# Thrust-Schematic.net
KiCad netlist of a schematic drawn in Altium Designer
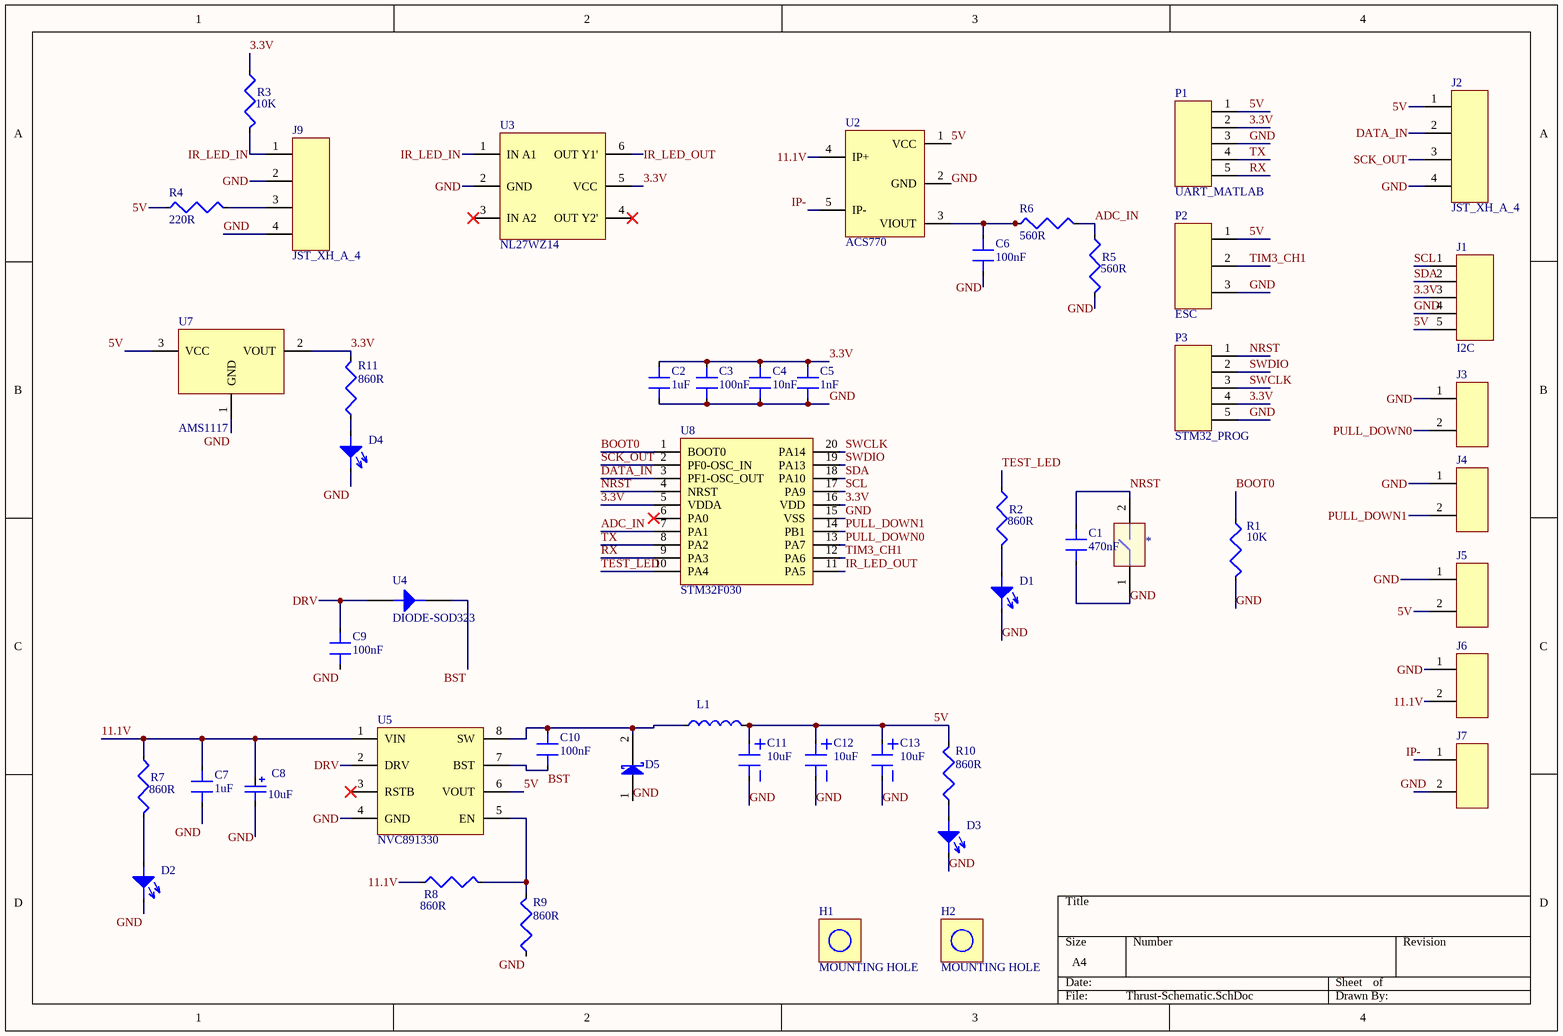
[diagram p0: Thrust-Schematic.SchDoc]

(export (version "E")
  (design (tool "Eeschema 10.0.6"))
  (components
    (comp (ref "*") (value "SWITCH") (footprint "SWITCH") (libsource (lib "Schlib1") (part "SWITCH")))
    (comp (ref "C1") (value "470nF") (footprint "RES0805") (libsource (lib "Schlib1") (part "CAP0805")))
    (comp (ref "C2") (value "1uF") (footprint "RES0805") (libsource (lib "Schlib1") (part "CAP0805")))
    (comp (ref "C3") (value "100nF") (footprint "RES0805") (libsource (lib "Schlib1") (part "CAP0805")))
    (comp (ref "C4") (value "10nF") (footprint "RES0805") (libsource (lib "Schlib1") (part "CAP0805")))
    (comp (ref "C5") (value "1nF") (footprint "RES0805") (libsource (lib "Schlib1") (part "CAP0805")))
    (comp (ref "C6") (value "100nF") (footprint "RES0805") (libsource (lib "Schlib1") (part "CAP0805")))
    (comp (ref "C7") (value "1uF") (footprint "RES0805") (libsource (lib "Schlib1") (part "CAP0805")))
    (comp (ref "C8")
      (value "10uF")
      (footprint "Cap_4x5.4_SMD")
      (libsource (lib "Schlib1") (part "SMD_Cap_4x5.4"))
    )
    (comp (ref "C9") (value "100nF") (footprint "RES0805") (libsource (lib "Schlib1") (part "CAP0805")))
    (comp (ref "C10") (value "100nF") (footprint "RES0805") (libsource (lib "Schlib1") (part "CAP0805")))
    (comp (ref "C11") (value "10uF") (footprint "CAP_THT") (libsource (lib "Schlib1") (part "CAP_THT")))
    (comp (ref "C12") (value "10uF") (footprint "CAP_THT") (libsource (lib "Schlib1") (part "CAP_THT")))
    (comp (ref "C13") (value "10uF") (footprint "CAP_THT") (libsource (lib "Schlib1") (part "CAP_THT")))
    (comp (ref "D1") (value "LED0805") (footprint "RES0805") (libsource (lib "Schlib1") (part "LED0805")))
    (comp (ref "D2") (value "LED0805") (footprint "RES0805") (libsource (lib "Schlib1") (part "LED0805")))
    (comp (ref "D3") (value "LED0805") (footprint "RES0805") (libsource (lib "Schlib1") (part "LED0805")))
    (comp (ref "D4") (value "LED0805") (footprint "RES0805") (libsource (lib "Schlib1") (part "LED0805")))
    (comp (ref "D5")
      (value "Diode")
      (footprint "Schottky")
      (description "Schottky Diode")
      (libsource (lib "Trig_Schlib") (part "Schottyky Diode"))
    )
    (comp (ref "H1")
      (value "MOUNTING HOLE")
      (footprint "MOUNTING HOLE")
      (libsource (lib "Trig_Schlib") (part "MOUNTING HOLE"))
    )
    (comp (ref "H2")
      (value "MOUNTING HOLE")
      (footprint "MOUNTING HOLE")
      (libsource (lib "Trig_Schlib") (part "MOUNTING HOLE"))
    )
    (comp (ref "J1") (value "I2C") (footprint "JST_XH_A_5") (libsource (lib "Schlib1") (part "JST_XH_A_5")))
    (comp (ref "J2")
      (value "JST_XH_A_4")
      (footprint "JST_XH_A_4")
      (libsource (lib "Schlib1") (part "JST_XH_A_4"))
    )
    (comp (ref "J3")
      (value "JST_XH_A_2")
      (footprint "JST_XH_A_2")
      (libsource (lib "Schlib1") (part "JST_XH_A_2"))
    )
    (comp (ref "J4")
      (value "JST_XH_A_2")
      (footprint "JST_XH_A_2")
      (libsource (lib "Schlib1") (part "JST_XH_A_2"))
    )
    (comp (ref "J5")
      (value "JST_XH_A_2")
      (footprint "JST_XH_A_2")
      (libsource (lib "Schlib1") (part "JST_XH_A_2"))
    )
    (comp (ref "J6") (value "XT60") (footprint "XT60") (libsource (lib "Schlib1") (part "XT60")))
    (comp (ref "J7") (value "XT60") (footprint "XT60") (libsource (lib "Schlib1") (part "XT60")))
    (comp (ref "J9")
      (value "JST_XH_A_4")
      (footprint "JST_XH_A_4")
      (libsource (lib "Schlib1") (part "JST_XH_A_4"))
    )
    (comp (ref "L1")
      (value "INDUCTOR")
      (footprint "IND-IHLP-1212BZ-11")
      (description "IHLP-1212BZ-11")
      (libsource (lib "Schlib1") (part "INDUCTOR"))
    )
    (comp (ref "P1")
      (value "UART_MATLAB")
      (footprint "Pin_Header_1x5")
      (libsource (lib "Schlib1") (part "Pin_Header_1x5"))
    )
    (comp (ref "P2")
      (value "ESC")
      (footprint "Pin_Header_1x3")
      (libsource (lib "Schlib1") (part "Pin_Header_1x3"))
    )
    (comp (ref "P3")
      (value "STM32_PROG")
      (footprint "Pin_Header_1x5")
      (libsource (lib "Schlib1") (part "Pin_Header_1x5"))
    )
    (comp (ref "R1") (value "10K") (footprint "RES0805") (libsource (lib "Schlib1") (part "RES0805")))
    (comp (ref "R2") (value "860R") (footprint "RES0805") (libsource (lib "Schlib1") (part "RES0805")))
    (comp (ref "R3") (value "10K") (footprint "RES0805") (libsource (lib "Schlib1") (part "RES0805")))
    (comp (ref "R4") (value "220R") (footprint "RES0805") (libsource (lib "Schlib1") (part "RES0805")))
    (comp (ref "R5") (value "560R") (footprint "RES0805") (libsource (lib "Schlib1") (part "RES0805")))
    (comp (ref "R6") (value "560R") (footprint "RES0805") (libsource (lib "Schlib1") (part "RES0805")))
    (comp (ref "R7") (value "860R") (footprint "RES0805") (libsource (lib "Schlib1") (part "RES0805")))
    (comp (ref "R8") (value "860R") (footprint "RES0805") (libsource (lib "Schlib1") (part "RES0805")))
    (comp (ref "R9") (value "860R") (footprint "RES0805") (libsource (lib "Schlib1") (part "RES0805")))
    (comp (ref "R10") (value "860R") (footprint "RES0805") (libsource (lib "Schlib1") (part "RES0805")))
    (comp (ref "R11") (value "860R") (footprint "RES0805") (libsource (lib "Schlib1") (part "RES0805")))
    (comp (ref "U2") (value "ACS770") (footprint "ACS770") (libsource (lib "Schlib1") (part "ACS770")))
    (comp (ref "U3") (value "NL27WZ14") (footprint "TSOP6") (libsource (lib "Schlib1") (part "NL27WZ14")))
    (comp (ref "U4")
      (value "DIODE-SOD323")
      (footprint "SODFL250X100-2N")
      (libsource (lib "Schlib1") (part "DIODE-SOD323"))
    )
    (comp (ref "U5") (value "NVC891330") (footprint "SOIC8") (libsource (lib "Schlib1") (part "NVC891330")))
    (comp (ref "U7") (value "AMS1117") (footprint "SOT223") (libsource (lib "Schlib1") (part "AMS1117")))
    (comp (ref "U8") (value "STM32F030") (footprint "TSOP20") (libsource (lib "Schlib1") (part "STM32F030")))
  )
  (nets
    (net (code "1") (name "/3.3V") (class "Default")
      (node (ref "C2") (pin "1") (pinfunction "*_1") (pintype "passive"))
      (node (ref "C3") (pin "1") (pinfunction "*_1") (pintype "passive"))
      (node (ref "C4") (pin "1") (pinfunction "*_1") (pintype "passive"))
      (node (ref "C5") (pin "1") (pinfunction "*_1") (pintype "passive"))
      (node (ref "J1") (pin "3") (pinfunction "*_3") (pintype "passive"))
      (node (ref "P1") (pin "2") (pinfunction "*_2") (pintype "passive"))
      (node (ref "P3") (pin "4") (pinfunction "*_4") (pintype "passive"))
      (node (ref "R11") (pin "1") (pinfunction "*_1") (pintype "passive"))
      (node (ref "R3") (pin "2") (pinfunction "*_2") (pintype "passive"))
      (node (ref "U3") (pin "5") (pinfunction "VCC_5") (pintype "passive"))
      (node (ref "U7") (pin "2") (pinfunction "VOUT_2") (pintype "passive"))
      (node (ref "U8") (pin "16") (pinfunction "VDD_16") (pintype "passive"))
      (node (ref "U8") (pin "5") (pinfunction "VDDA_5") (pintype "passive"))
    )
    (net (code "2") (name "/5V") (class "Default")
      (node (ref "C11") (pin "1") (pinfunction "*_1") (pintype "passive"))
      (node (ref "C12") (pin "1") (pinfunction "*_1") (pintype "passive"))
      (node (ref "C13") (pin "1") (pinfunction "*_1") (pintype "passive"))
      (node (ref "J1") (pin "5") (pinfunction "*_5") (pintype "passive"))
      (node (ref "J2") (pin "1") (pinfunction "*_1") (pintype "passive"))
      (node (ref "J5") (pin "2") (pinfunction "*_2") (pintype "passive"))
      (node (ref "L1") (pin "2") (pinfunction "*_2") (pintype "passive"))
      (node (ref "P1") (pin "1") (pinfunction "*_1") (pintype "passive"))
      (node (ref "P2") (pin "1") (pinfunction "*_1") (pintype "passive"))
      (node (ref "R10") (pin "1") (pinfunction "*_1") (pintype "passive"))
      (node (ref "R4") (pin "2") (pinfunction "*_2") (pintype "passive"))
      (node (ref "U2") (pin "1") (pinfunction "VCC_1") (pintype "passive"))
      (node (ref "U5") (pin "6") (pinfunction "VOUT_6") (pintype "passive"))
      (node (ref "U7") (pin "3") (pinfunction "VCC_3") (pintype "passive"))
    )
    (net (code "3") (name "/11.1V") (class "Default")
      (node (ref "C7") (pin "2") (pinfunction "*_2") (pintype "passive"))
      (node (ref "C8") (pin "1") (pinfunction "1_1") (pintype "passive"))
      (node (ref "J6") (pin "2") (pinfunction "BOOT16_2") (pintype "passive"))
      (node (ref "R7") (pin "2") (pinfunction "*_2") (pintype "passive"))
      (node (ref "R8") (pin "2") (pinfunction "*_2") (pintype "passive"))
      (node (ref "U2") (pin "4") (pinfunction "IP+_4") (pintype "passive"))
      (node (ref "U5") (pin "1") (pinfunction "VIN_1") (pintype "passive"))
    )
    (net (code "4") (name "/ADC_IN") (class "Default")
      (node (ref "R5") (pin "2") (pinfunction "*_2") (pintype "passive"))
      (node (ref "R6") (pin "1") (pinfunction "*_1") (pintype "passive"))
      (node (ref "U8") (pin "7") (pinfunction "PA1_7") (pintype "passive"))
    )
    (net (code "5") (name "/BOOT0") (class "Default")
      (node (ref "R1") (pin "2") (pinfunction "*_2") (pintype "passive"))
      (node (ref "U8") (pin "1") (pinfunction "BOOT0_1") (pintype "passive"))
    )
    (net (code "6") (name "/BST") (class "Default")
      (node (ref "C10") (pin "1") (pinfunction "*_1") (pintype "passive"))
      (node (ref "U4") (pin "2") (pinfunction "?_2") (pintype "passive"))
      (node (ref "U5") (pin "7") (pinfunction "BST_7") (pintype "passive"))
    )
    (net (code "7") (name "/DATA_IN") (class "Default")
      (node (ref "J2") (pin "2") (pinfunction "*_2") (pintype "passive"))
      (node (ref "U8") (pin "3") (pinfunction "PF1-OSC_OUT_3") (pintype "passive"))
    )
    (net (code "8") (name "/DRV") (class "Default")
      (node (ref "C9") (pin "2") (pinfunction "*_2") (pintype "passive"))
      (node (ref "U4") (pin "1") (pinfunction "?_1") (pintype "passive"))
      (node (ref "U5") (pin "2") (pinfunction "DRV_2") (pintype "passive"))
    )
    (net (code "9") (name "/GND") (class "Default")
      (node (ref "*") (pin "1") (pinfunction "*_1") (pintype "passive"))
      (node (ref "C1") (pin "1") (pinfunction "*_1") (pintype "passive"))
      (node (ref "C11") (pin "2") (pinfunction "*_2") (pintype "passive"))
      (node (ref "C12") (pin "2") (pinfunction "*_2") (pintype "passive"))
      (node (ref "C13") (pin "2") (pinfunction "*_2") (pintype "passive"))
      (node (ref "C2") (pin "2") (pinfunction "*_2") (pintype "passive"))
      (node (ref "C3") (pin "2") (pinfunction "*_2") (pintype "passive"))
      (node (ref "C4") (pin "2") (pinfunction "*_2") (pintype "passive"))
      (node (ref "C5") (pin "2") (pinfunction "*_2") (pintype "passive"))
      (node (ref "C6") (pin "2") (pinfunction "*_2") (pintype "passive"))
      (node (ref "C7") (pin "1") (pinfunction "*_1") (pintype "passive"))
      (node (ref "C8") (pin "2") (pinfunction "2_2") (pintype "passive"))
      (node (ref "C9") (pin "1") (pinfunction "*_1") (pintype "passive"))
      (node (ref "D1") (pin "2") (pinfunction "*_2") (pintype "passive"))
      (node (ref "D2") (pin "2") (pinfunction "*_2") (pintype "passive"))
      (node (ref "D3") (pin "2") (pinfunction "*_2") (pintype "passive"))
      (node (ref "D4") (pin "2") (pinfunction "*_2") (pintype "passive"))
      (node (ref "D5") (pin "1") (pinfunction "0_1") (pintype "passive"))
      (node (ref "J1") (pin "4") (pinfunction "*_4") (pintype "passive"))
      (node (ref "J2") (pin "4") (pinfunction "*_4") (pintype "passive"))
      (node (ref "J3") (pin "1") (pinfunction "*_1") (pintype "passive"))
      (node (ref "J4") (pin "1") (pinfunction "*_1") (pintype "passive"))
      (node (ref "J5") (pin "1") (pinfunction "*_1") (pintype "passive"))
      (node (ref "J6") (pin "1") (pinfunction "BOOT15_1") (pintype "passive"))
      (node (ref "J7") (pin "2") (pinfunction "BOOT16_2") (pintype "passive"))
      (node (ref "J9") (pin "2") (pinfunction "*_2") (pintype "passive"))
      (node (ref "J9") (pin "4") (pinfunction "*_4") (pintype "passive"))
      (node (ref "P1") (pin "3") (pinfunction "*_3") (pintype "passive"))
      (node (ref "P2") (pin "3") (pinfunction "*_3") (pintype "passive"))
      (node (ref "P3") (pin "5") (pinfunction "*_5") (pintype "passive"))
      (node (ref "R1") (pin "1") (pinfunction "*_1") (pintype "passive"))
      (node (ref "R5") (pin "1") (pinfunction "*_1") (pintype "passive"))
      (node (ref "R9") (pin "2") (pinfunction "*_2") (pintype "passive"))
      (node (ref "U3") (pin "2") (pinfunction "GND_2") (pintype "passive"))
      (node (ref "U5") (pin "4") (pinfunction "GND_4") (pintype "passive"))
      (node (ref "U7") (pin "1") (pinfunction "GND_1") (pintype "passive"))
      (node (ref "U8") (pin "15") (pinfunction "VSS_15") (pintype "passive"))
    )
    (net (code "10") (name "/IP-") (class "Default")
      (node (ref "J7") (pin "1") (pinfunction "BOOT15_1") (pintype "passive"))
      (node (ref "U2") (pin "5") (pinfunction "IP-_5") (pintype "passive"))
    )
    (net (code "11") (name "/IR_LED_IN") (class "Default")
      (node (ref "J9") (pin "1") (pinfunction "*_1") (pintype "passive"))
      (node (ref "R3") (pin "1") (pinfunction "*_1") (pintype "passive"))
      (node (ref "U3") (pin "1") (pinfunction "IN_A1_1") (pintype "passive"))
    )
    (net (code "12") (name "/IR_LED_OUT") (class "Default")
      (node (ref "U3") (pin "6") (pinfunction "OUT_Y1'_6") (pintype "passive"))
      (node (ref "U8") (pin "11") (pinfunction "PA5_11") (pintype "passive"))
    )
    (net (code "13") (name "/NRST") (class "Default")
      (node (ref "*") (pin "2") (pinfunction "*_2") (pintype "passive"))
      (node (ref "C1") (pin "2") (pinfunction "*_2") (pintype "passive"))
      (node (ref "P3") (pin "1") (pinfunction "*_1") (pintype "passive"))
      (node (ref "U8") (pin "4") (pinfunction "NRST_4") (pintype "passive"))
    )
    (net (code "14") (name "/PULL_DOWN0") (class "Default")
      (node (ref "J3") (pin "2") (pinfunction "*_2") (pintype "passive"))
      (node (ref "U8") (pin "13") (pinfunction "PA7_13") (pintype "passive"))
    )
    (net (code "15") (name "/PULL_DOWN1") (class "Default")
      (node (ref "J4") (pin "2") (pinfunction "*_2") (pintype "passive"))
      (node (ref "U8") (pin "14") (pinfunction "PB1_14") (pintype "passive"))
    )
    (net (code "16") (name "/RX") (class "Default")
      (node (ref "P1") (pin "5") (pinfunction "*_5") (pintype "passive"))
      (node (ref "U8") (pin "9") (pinfunction "PA3_9") (pintype "passive"))
    )
    (net (code "17") (name "/SCK_OUT") (class "Default")
      (node (ref "J2") (pin "3") (pinfunction "*_3") (pintype "passive"))
      (node (ref "U8") (pin "2") (pinfunction "PF0-OSC_IN_2") (pintype "passive"))
    )
    (net (code "18") (name "/SCL") (class "Default")
      (node (ref "J1") (pin "1") (pinfunction "*_1") (pintype "passive"))
      (node (ref "U8") (pin "17") (pinfunction "PA9_17") (pintype "passive"))
    )
    (net (code "19") (name "/SDA") (class "Default")
      (node (ref "J1") (pin "2") (pinfunction "*_2") (pintype "passive"))
      (node (ref "U8") (pin "18") (pinfunction "PA10_18") (pintype "passive"))
    )
    (net (code "20") (name "/SWCLK") (class "Default")
      (node (ref "P3") (pin "3") (pinfunction "*_3") (pintype "passive"))
      (node (ref "U8") (pin "20") (pinfunction "PA14_20") (pintype "passive"))
    )
    (net (code "21") (name "/SWDIO") (class "Default")
      (node (ref "P3") (pin "2") (pinfunction "*_2") (pintype "passive"))
      (node (ref "U8") (pin "19") (pinfunction "PA13_19") (pintype "passive"))
    )
    (net (code "22") (name "/TEST_LED") (class "Default")
      (node (ref "R2") (pin "2") (pinfunction "*_2") (pintype "passive"))
      (node (ref "U8") (pin "10") (pinfunction "PA4_10") (pintype "passive"))
    )
    (net (code "23") (name "/TIM3_CH1") (class "Default")
      (node (ref "P2") (pin "2") (pinfunction "*_2") (pintype "passive"))
      (node (ref "U8") (pin "12") (pinfunction "PA6_12") (pintype "passive"))
    )
    (net (code "24") (name "/TX") (class "Default")
      (node (ref "P1") (pin "4") (pinfunction "*_4") (pintype "passive"))
      (node (ref "U8") (pin "8") (pinfunction "PA2_8") (pintype "passive"))
    )
    (net (code "25") (name "Net-(D1-*-Pad1)") (class "Default")
      (node (ref "D1") (pin "1") (pinfunction "*_1") (pintype "passive"))
      (node (ref "R2") (pin "1") (pinfunction "*_1") (pintype "passive"))
    )
    (net (code "26") (name "Net-(D2-*-Pad1)") (class "Default")
      (node (ref "D2") (pin "1") (pinfunction "*_1") (pintype "passive"))
      (node (ref "R7") (pin "1") (pinfunction "*_1") (pintype "passive"))
    )
    (net (code "27") (name "Net-(D3-*-Pad1)") (class "Default")
      (node (ref "D3") (pin "1") (pinfunction "*_1") (pintype "passive"))
      (node (ref "R10") (pin "2") (pinfunction "*_2") (pintype "passive"))
    )
    (net (code "28") (name "Net-(D4-*-Pad1)") (class "Default")
      (node (ref "D4") (pin "1") (pinfunction "*_1") (pintype "passive"))
      (node (ref "R11") (pin "2") (pinfunction "*_2") (pintype "passive"))
    )
    (net (code "29") (name "Net-(J9-*-Pad3)") (class "Default")
      (node (ref "J9") (pin "3") (pinfunction "*_3") (pintype "passive"))
      (node (ref "R4") (pin "1") (pinfunction "*_1") (pintype "passive"))
    )
    (net (code "30") (name "Net-(U2-VIOUT)") (class "Default")
      (node (ref "C6") (pin "1") (pinfunction "*_1") (pintype "passive"))
      (node (ref "R6") (pin "2") (pinfunction "*_2") (pintype "passive"))
      (node (ref "U2") (pin "3") (pinfunction "VIOUT_3") (pintype "passive"))
    )
    (net (code "31") (name "Net-(U5-EN)") (class "Default")
      (node (ref "R8") (pin "1") (pinfunction "*_1") (pintype "passive"))
      (node (ref "R9") (pin "1") (pinfunction "*_1") (pintype "passive"))
      (node (ref "U5") (pin "5") (pinfunction "EN_5") (pintype "passive"))
    )
    (net (code "32") (name "Net-(U5-SW)") (class "Default")
      (node (ref "C10") (pin "2") (pinfunction "*_2") (pintype "passive"))
      (node (ref "D5") (pin "2") (pinfunction "0_2") (pintype "passive"))
      (node (ref "L1") (pin "1") (pinfunction "*_1") (pintype "passive"))
      (node (ref "U5") (pin "8") (pinfunction "SW_8") (pintype "passive"))
    )
    (net (code "33") (name "unconnected-(U2-GND-Pad2)") (class "Default")
      (node (ref "U2") (pin "2") (pinfunction "GND_2") (pintype "passive"))
    )
    (net (code "34") (name "unconnected-(U3-IN_A2-Pad3)") (class "Default")
      (node (ref "U3") (pin "3") (pinfunction "IN_A2_3") (pintype "passive+no_connect"))
    )
    (net (code "35") (name "unconnected-(U3-OUT_Y2'-Pad4)") (class "Default")
      (node (ref "U3") (pin "4") (pinfunction "OUT_Y2'_4") (pintype "passive+no_connect"))
    )
    (net (code "36") (name "unconnected-(U5-RSTB-Pad3)") (class "Default")
      (node (ref "U5") (pin "3") (pinfunction "RSTB_3") (pintype "passive+no_connect"))
    )
    (net (code "37") (name "unconnected-(U8-PA0-Pad6)") (class "Default")
      (node (ref "U8") (pin "6") (pinfunction "PA0_6") (pintype "passive+no_connect"))
    )
  )
)
